# logica_de_arranque.net
KiCad netlist of a schematic drawn in Altium Designer
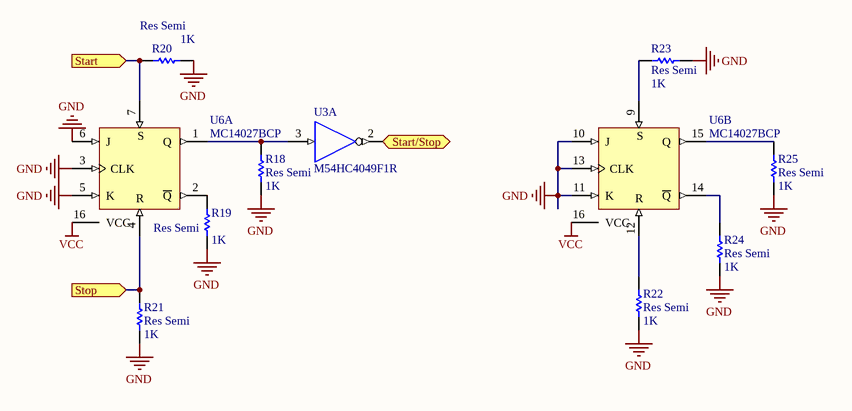
[diagram p0: logica de arranque.SchDoc]

(export (version "E")
  (design (tool "Eeschema 10.0.6"))
  (components
    (comp (ref "R18")
      (value "Res Semi")
      (footprint "2012[0805]")
      (description "Semiconductor Resistor")
      (fields (field (name "ALTIUM_VALUE") "1K") (field (name "PUBLISHER") "Altium Limited"))
      (libsource (lib "Miscellaneous Devices") (part "Res Semi"))
    )
    (comp (ref "R19")
      (value "Res Semi")
      (footprint "2012[0805]")
      (description "Semiconductor Resistor")
      (fields (field (name "ALTIUM_VALUE") "1K") (field (name "PUBLISHER") "Altium Limited"))
      (libsource (lib "Miscellaneous Devices") (part "Res Semi"))
    )
    (comp (ref "R20")
      (value "Res Semi")
      (footprint "2012[0805]")
      (description "Semiconductor Resistor")
      (fields (field (name "ALTIUM_VALUE") "1K") (field (name "PUBLISHER") "Altium Limited"))
      (libsource (lib "Miscellaneous Devices") (part "Res Semi"))
    )
    (comp (ref "R21")
      (value "Res Semi")
      (footprint "2012[0805]")
      (description "Semiconductor Resistor")
      (fields (field (name "ALTIUM_VALUE") "1K") (field (name "PUBLISHER") "Altium Limited"))
      (libsource (lib "Miscellaneous Devices") (part "Res Semi"))
    )
    (comp (ref "R22")
      (value "Res Semi")
      (footprint "2012[0805]")
      (description "Semiconductor Resistor")
      (fields (field (name "ALTIUM_VALUE") "1K") (field (name "PUBLISHER") "Altium Limited"))
      (libsource (lib "Miscellaneous Devices") (part "Res Semi"))
    )
    (comp (ref "R23")
      (value "Res Semi")
      (footprint "2012[0805]")
      (description "Semiconductor Resistor")
      (fields (field (name "ALTIUM_VALUE") "1K") (field (name "PUBLISHER") "Altium Limited"))
      (libsource (lib "Miscellaneous Devices") (part "Res Semi"))
    )
    (comp (ref "R24")
      (value "Res Semi")
      (footprint "2012[0805]")
      (description "Semiconductor Resistor")
      (fields (field (name "ALTIUM_VALUE") "1K") (field (name "PUBLISHER") "Altium Limited"))
      (libsource (lib "Miscellaneous Devices") (part "Res Semi"))
    )
    (comp (ref "R25")
      (value "Res Semi")
      (footprint "2012[0805]")
      (description "Semiconductor Resistor")
      (fields (field (name "ALTIUM_VALUE") "1K") (field (name "PUBLISHER") "Altium Limited"))
      (libsource (lib "Miscellaneous Devices") (part "Res Semi"))
    )
    (comp (ref "U3")
      (value "M54HC4049F1R")
      (footprint "DIP16")
      (description "Hex Buffer/Converter Invertering")
      (fields (field (name "PUBLISHER") "Altium Limited"))
      (libsource (lib "ST Logic Gate") (part "M54HC4049F1R"))
    )
    (comp (ref "U6")
      (value "MC14027BCP")
      (footprint "648-08")
      (description "Dual J-K Flip-Flop")
      (fields (field (name "PUBLISHER") "Altium Limited"))
      (libsource (lib "ON Semi Logic Flip-Flop") (part "MC14027BCP"))
    )
  )
  (nets
    (net (code "1") (name "/Start") (class "Default")
      (node (ref "R20") (pin "1") (pinfunction "1_1") (pintype "passive"))
      (node (ref "U6") (pin "7") (pinfunction "S_7") (pintype "input"))
    )
    (net (code "2") (name "/Start{slash}Stop") (class "Default")
      (node (ref "U3") (pin "2") (pinfunction "Y_2") (pintype "output"))
    )
    (net (code "3") (name "/Stop") (class "Default")
      (node (ref "R21") (pin "2") (pinfunction "2_2") (pintype "passive"))
      (node (ref "U6") (pin "4") (pinfunction "R_4") (pintype "input"))
    )
    (net (code "4") (name "GND") (class "Default")
      (node (ref "R18") (pin "2") (pinfunction "2_2") (pintype "passive"))
      (node (ref "R19") (pin "1") (pinfunction "1_1") (pintype "passive"))
      (node (ref "R20") (pin "2") (pinfunction "2_2") (pintype "passive"))
      (node (ref "R21") (pin "1") (pinfunction "1_1") (pintype "passive"))
      (node (ref "R22") (pin "1") (pinfunction "1_1") (pintype "passive"))
      (node (ref "R23") (pin "2") (pinfunction "2_2") (pintype "passive"))
      (node (ref "R24") (pin "1") (pinfunction "1_1") (pintype "passive"))
      (node (ref "R25") (pin "1") (pinfunction "1_1") (pintype "passive"))
      (node (ref "U3") (pin "8") (pinfunction "GND_8") (pintype "power_in"))
      (node (ref "U6") (pin "10") (pinfunction "J_10") (pintype "input"))
      (node (ref "U6") (pin "11") (pinfunction "K_11") (pintype "input"))
      (node (ref "U6") (pin "13") (pinfunction "CLK_13") (pintype "input"))
      (node (ref "U6") (pin "3") (pinfunction "CLK_3") (pintype "input"))
      (node (ref "U6") (pin "5") (pinfunction "K_5") (pintype "input"))
      (node (ref "U6") (pin "6") (pinfunction "J_6") (pintype "input"))
      (node (ref "U6") (pin "8") (pinfunction "GND_8") (pintype "power_in"))
    )
    (net (code "5") (name "Net-(U3A-A)") (class "Default")
      (node (ref "R18") (pin "1") (pinfunction "1_1") (pintype "passive"))
      (node (ref "U3") (pin "3") (pinfunction "A_3") (pintype "input"))
      (node (ref "U6") (pin "1") (pinfunction "Q_1") (pintype "output"))
    )
    (net (code "6") (name "Net-(U6A-~{Q})") (class "Default")
      (node (ref "R19") (pin "2") (pinfunction "2_2") (pintype "passive"))
      (node (ref "U6") (pin "2") (pinfunction "~{Q}_2") (pintype "output"))
    )
    (net (code "7") (name "Net-(U6B-Q)") (class "Default")
      (node (ref "R25") (pin "2") (pinfunction "2_2") (pintype "passive"))
      (node (ref "U6") (pin "15") (pinfunction "Q_15") (pintype "output"))
    )
    (net (code "8") (name "Net-(U6B-R)") (class "Default")
      (node (ref "R22") (pin "2") (pinfunction "2_2") (pintype "passive"))
      (node (ref "U6") (pin "12") (pinfunction "R_12") (pintype "input"))
    )
    (net (code "9") (name "Net-(U6B-S)") (class "Default")
      (node (ref "R23") (pin "1") (pinfunction "1_1") (pintype "passive"))
      (node (ref "U6") (pin "9") (pinfunction "S_9") (pintype "input"))
    )
    (net (code "10") (name "Net-(U6B-~{Q})") (class "Default")
      (node (ref "R24") (pin "2") (pinfunction "2_2") (pintype "passive"))
      (node (ref "U6") (pin "14") (pinfunction "~{Q}_14") (pintype "output"))
    )
    (net (code "11") (name "VCC") (class "Default")
      (node (ref "U3") (pin "1") (pinfunction "VCC_1") (pintype "power_in"))
      (node (ref "U6") (pin "16") (pinfunction "VCC_16") (pintype "power_in"))
    )
  )
)
